# Cloud_Buck_Sch.net
KiCad netlist of a schematic drawn in Altium Designer
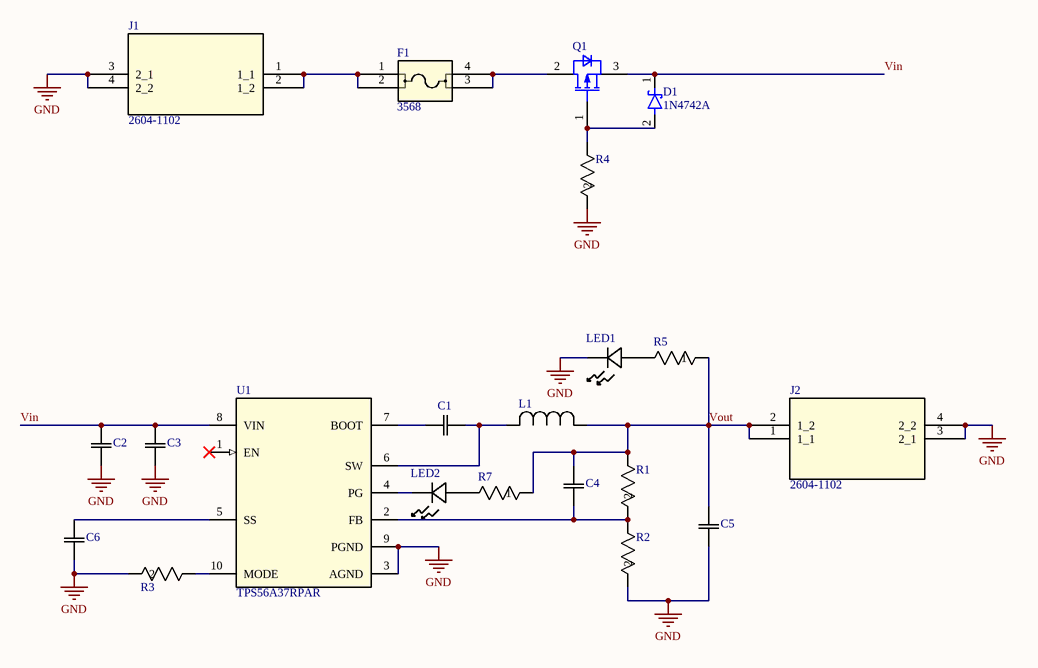
[diagram p0: Cloud_Buck_Sch.SchDoc]

(export (version "E")
  (design (tool "Eeschema 10.0.6"))
  (components
    (comp (ref "C1")
      (value "EMK107B7104KA-T")
      (footprint "cap_UMK107ABJ474KA-T_TAY")
      (description "Description")
      (fields (field (name "COPYRIGHT") "Copyright (C) 2025 Ultra Librarian. All rights reserved."))
      (libsource (lib "Cloud_ Buck_Sym") (part "EMK107B7104KA-T"))
    )
    (comp (ref "C2")
      (value "MSASU32MSB5106KPNA01")
      (footprint "CAP_MSAS32-M_TAY")
      (description "Description")
      (fields (field (name "COPYRIGHT") "Copyright (C) 2026 Ultra Librarian. All rights reserved."))
      (libsource (lib "Cloud_ Buck_Sym") (part "MSASU32MSB5106KPNA01"))
    )
    (comp (ref "C3")
      (value "CC0805KRX7R9BB104")
      (footprint "CC0805N_YAG")
      (description "Description")
      (fields (field (name "COPYRIGHT") "Copyright (C) 2025 Ultra Librarian. All rights reserved."))
      (libsource (lib "Cloud_ Buck_Sym") (part "CC0805KRX7R9BB104"))
    )
    (comp (ref "C4")
      (value "GRM1885C1H101JA01D")
      (footprint "CAP_188_MUR")
      (description "CAP CER 100PF 50V C0G/NP0 0603")
      (fields (field (name "COPYRIGHT") "Copyright (C) 2026 Ultra Librarian. All rights reserved."))
      (libsource (lib "Cloud_ Buck_Sym") (part "GRM1885C1H101JA01D"))
    )
    (comp (ref "C5")
      (value "GRM32ER61C476KE15L")
      (footprint "G-32_MUR")
      (description "Description")
      (fields (field (name "COPYRIGHT") "Copyright (C) 2025 Ultra Librarian. All rights reserved."))
      (libsource (lib "Cloud_ Buck_Sym") (part "GRM32ER61C476KE15L"))
    )
    (comp (ref "C6")
      (value "GRM155R71C223KA01D")
      (footprint "G-155_MUR")
      (description "Description")
      (fields (field (name "COPYRIGHT") "Copyright (C) 2026 Ultra Librarian. All rights reserved."))
      (libsource (lib "Cloud_ Buck_Sym") (part "GRM155R71C223KA01D"))
    )
    (comp (ref "D1")
      (value "1N4742A")
      (footprint "DIOAD1036W78L463D237")
      (description "Zener Diode, Single, Two Terminal, 12V V(Z), 5%, DO-204AL")
      (fields (field (name "MF") "ON Semiconductor"))
      (libsource (lib "Cloud_ Buck_Sym") (part "1N4742A"))
    )
    (comp (ref "F1")
      (value "3568")
      (footprint "3568_KEY")
      (description "Description")
      (fields (field (name "COPYRIGHT") "Copyright (C) 2026 Ultra Librarian. All rights reserved."))
      (libsource (lib "Cloud_ Buck_Sym") (part "3568"))
    )
    (comp (ref "J1")
      (value "2604-1102")
      (footprint "CONN2_2604-1102_WAG")
      (description "Description")
      (fields (field (name "COPYRIGHT") "Copyright (C) 2025 Ultra Librarian. All rights reserved."))
      (libsource (lib "Cloud_ Buck_Sym") (part "2604-1102"))
    )
    (comp (ref "J2")
      (value "2604-1102")
      (footprint "CONN2_2604-1102_WAG")
      (description "Description")
      (fields (field (name "COPYRIGHT") "Copyright (C) 2025 Ultra Librarian. All rights reserved."))
      (libsource (lib "") (part "2604-1102_1"))
    )
    (comp (ref "L1")
      (value "XAL7070-332MEC")
      (footprint "IND_XAL7070_COC")
      (description "Description")
      (fields (field (name "COPYRIGHT") "Copyright (C) 2026 Ultra Librarian. All rights reserved."))
      (libsource (lib "Cloud_ Buck_Sym") (part "XAL7070-332MEC"))
    )
    (comp (ref "LED1")
      (value "LTST-C170KGKT")
      (footprint "LED_LTST-C170KGKT_LTO")
      (description "Description")
      (fields (field (name "COPYRIGHT") "Copyright (C) 2025 Ultra Librarian. All rights reserved."))
      (libsource (lib "Cloud_ Buck_Sym") (part "LTST-C170KGKT"))
    )
    (comp (ref "LED2")
      (value "LTST-C170KGKT")
      (footprint "LED_LTST-C170KGKT_LTO")
      (description "Description")
      (fields (field (name "COPYRIGHT") "Copyright (C) 2025 Ultra Librarian. All rights reserved."))
      (libsource (lib "Cloud_ Buck_Sym") (part "LTST-C170KGKT"))
    )
    (comp (ref "Q1")
      (value "IRF4905")
      (footprint "IFX-PG-TO220-3-904-1")
      (description "OptiMOS - P2 Power-Transistor, P-channel-Enhancement mode, VDS -30V")
      (fields (field (name "MANUFACTURER") "Infineon Technologies"))
      (libsource (lib "Cloud_ Buck_Sym") (part "IRF4905"))
    )
    (comp (ref "R1")
      (value "ERJ-6ENF7322V")
      (footprint "RC0805N_PAN")
      (description "Description")
      (fields (field (name "COPYRIGHT") "Copyright (C) 2026 Ultra Librarian. All rights reserved."))
      (libsource (lib "Cloud_ Buck_Sym") (part "ERJ-6ENF7322V"))
    )
    (comp (ref "R2")
      (value "CRCW060310K0FKEA")
      (footprint "RES_CRCW_0603")
      (description "D11/CRCW0603 100 10K 1% ET1 e3")
      (fields (field (name "COPYRIGHT") "Copyright (C) 2025 Ultra Librarian. All rights reserved."))
      (libsource (lib "Cloud_ Buck_Sym") (part "CRCW060310K0FKEA"))
    )
    (comp (ref "R3")
      (value "CRCW040252K3FKED")
      (footprint "RES_CRCW_0402")
      (description "D10/CRCW0402 100 52K3 1% ET7 e3")
      (fields (field (name "COPYRIGHT") "Copyright (C) 2026 Ultra Librarian. All rights reserved."))
      (libsource (lib "Cloud_ Buck_Sym") (part "CRCW040252K3FKED"))
    )
    (comp (ref "R4")
      (value "CRCW080510K0FKEA")
      (footprint "RES_CRCW_0805")
      (description "D12/CRCW0805 100 10K 1% ET1 e3")
      (fields (field (name "COPYRIGHT") "Copyright (C) 2025 Ultra Librarian. All rights reserved."))
      (libsource (lib "Cloud_ Buck_Sym") (part "CRCW080510K0FKEA"))
    )
    (comp (ref "R5")
      (value "RC0805FR-071K5L")
      (footprint "RC0805N_YAG")
      (description "Description")
      (fields (field (name "COPYRIGHT") "Copyright (C) 2025 Ultra Librarian. All rights reserved."))
      (libsource (lib "Cloud_ Buck_Sym") (part "RC0805FR-071K5L"))
    )
    (comp (ref "R7")
      (value "RC0805FR-071K5L")
      (footprint "RC0805N_YAG")
      (description "Description")
      (fields (field (name "COPYRIGHT") "Copyright (C) 2025 Ultra Librarian. All rights reserved."))
      (libsource (lib "Cloud_ Buck_Sym") (part "RC0805FR-071K5L"))
    )
    (comp (ref "U1")
      (value "TPS56A37RPAR")
      (footprint "RPA0010A-MFG")
      (description "4.5V to 28V input, 10A synchronous buck converter 10-VQFN-HR -40 to 150")
      (fields (field (name "COPYRIGHT") "Copyright (C) 2026 Ultra Librarian. All rights reserved."))
      (libsource (lib "Cloud_ Buck_Sym") (part "TPS56A37RPAR"))
    )
  )
  (nets
    (net (code "1") (name "/Vin") (class "Default")
      (node (ref "C2") (pin "2") (pinfunction "2_2") (pintype "passive"))
      (node (ref "C3") (pin "2") (pinfunction "2_2") (pintype "passive"))
      (node (ref "D1") (pin "1") (pinfunction "K_1") (pintype "passive"))
      (node (ref "Q1") (pin "3") (pinfunction "SOURCE_3") (pintype "passive"))
      (node (ref "U1") (pin "8") (pinfunction "VIN_8") (pintype "power_in"))
    )
    (net (code "2") (name "/Vout") (class "Default")
      (node (ref "C4") (pin "2") (pinfunction "2_2") (pintype "passive"))
      (node (ref "C5") (pin "2") (pinfunction "2_2") (pintype "passive"))
      (node (ref "J2") (pin "1") (pinfunction "1_1_1") (pintype "passive"))
      (node (ref "J2") (pin "2") (pinfunction "1_2_2") (pintype "passive"))
      (node (ref "L1") (pin "1") (pinfunction "1_1") (pintype "passive"))
      (node (ref "R1") (pin "1") (pinfunction "1_1") (pintype "passive"))
      (node (ref "R5") (pin "1") (pinfunction "1_1") (pintype "passive"))
      (node (ref "R7") (pin "1") (pinfunction "1_1") (pintype "passive"))
    )
    (net (code "3") (name "GND") (class "Default")
      (node (ref "C2") (pin "1") (pinfunction "1_1") (pintype "passive"))
      (node (ref "C3") (pin "1") (pinfunction "1_1") (pintype "passive"))
      (node (ref "C5") (pin "1") (pinfunction "1_1") (pintype "passive"))
      (node (ref "C6") (pin "1") (pinfunction "1_1") (pintype "passive"))
      (node (ref "J1") (pin "3") (pinfunction "2_1_3") (pintype "passive"))
      (node (ref "J1") (pin "4") (pinfunction "2_2_4") (pintype "passive"))
      (node (ref "J2") (pin "3") (pinfunction "2_1_3") (pintype "passive"))
      (node (ref "J2") (pin "4") (pinfunction "2_2_4") (pintype "passive"))
      (node (ref "LED1") (pin "1") (pinfunction "1_1") (pintype "passive"))
      (node (ref "R2") (pin "2") (pinfunction "2_2") (pintype "passive"))
      (node (ref "R3") (pin "2") (pinfunction "2_2") (pintype "passive"))
      (node (ref "R4") (pin "2") (pinfunction "2_2") (pintype "passive"))
      (node (ref "U1") (pin "3") (pinfunction "AGND_3") (pintype "power_in"))
      (node (ref "U1") (pin "9") (pinfunction "PGND_9") (pintype "power_in"))
    )
    (net (code "4") (name "Net-(D1-A)") (class "Default")
      (node (ref "D1") (pin "2") (pinfunction "A_2") (pintype "passive"))
      (node (ref "Q1") (pin "1") (pinfunction "GATE_1") (pintype "passive"))
      (node (ref "R4") (pin "1") (pinfunction "1_1") (pintype "passive"))
    )
    (net (code "5") (name "Net-(J1-1_1)") (class "Default")
      (node (ref "F1") (pin "1") (pinfunction "1_1") (pintype "passive"))
      (node (ref "F1") (pin "2") (pinfunction "2_2") (pintype "passive"))
      (node (ref "J1") (pin "1") (pinfunction "1_1_1") (pintype "passive"))
      (node (ref "J1") (pin "2") (pinfunction "1_2_2") (pintype "passive"))
    )
    (net (code "6") (name "Net-(LED1-Pad2)") (class "Default")
      (node (ref "LED1") (pin "2") (pinfunction "2_2") (pintype "passive"))
      (node (ref "R5") (pin "2") (pinfunction "2_2") (pintype "passive"))
    )
    (net (code "7") (name "Net-(LED2-Pad2)") (class "Default")
      (node (ref "LED2") (pin "2") (pinfunction "2_2") (pintype "passive"))
      (node (ref "R7") (pin "2") (pinfunction "2_2") (pintype "passive"))
    )
    (net (code "8") (name "Net-(Q1-DRAIN)") (class "Default")
      (node (ref "F1") (pin "3") (pinfunction "3_3") (pintype "passive"))
      (node (ref "F1") (pin "4") (pinfunction "4_4") (pintype "passive"))
      (node (ref "Q1") (pin "2") (pinfunction "DRAIN_2") (pintype "passive"))
    )
    (net (code "9") (name "Net-(U1-BOOT)") (class "Default")
      (node (ref "C1") (pin "1") (pinfunction "1_1") (pintype "passive"))
      (node (ref "U1") (pin "7") (pinfunction "BOOT_7") (pintype "passive"))
    )
    (net (code "10") (name "Net-(U1-FB)") (class "Default")
      (node (ref "C4") (pin "1") (pinfunction "1_1") (pintype "passive"))
      (node (ref "R1") (pin "2") (pinfunction "2_2") (pintype "passive"))
      (node (ref "R2") (pin "1") (pinfunction "1_1") (pintype "passive"))
      (node (ref "U1") (pin "2") (pinfunction "FB_2") (pintype "passive"))
    )
    (net (code "11") (name "Net-(U1-MODE)") (class "Default")
      (node (ref "R3") (pin "1") (pinfunction "1_1") (pintype "passive"))
      (node (ref "U1") (pin "10") (pinfunction "MODE_10") (pintype "passive"))
    )
    (net (code "12") (name "Net-(U1-PG)") (class "Default")
      (node (ref "LED2") (pin "1") (pinfunction "1_1") (pintype "passive"))
      (node (ref "U1") (pin "4") (pinfunction "PG_4") (pintype "open_collector"))
    )
    (net (code "13") (name "Net-(U1-SS)") (class "Default")
      (node (ref "C6") (pin "2") (pinfunction "2_2") (pintype "passive"))
      (node (ref "U1") (pin "5") (pinfunction "SS_5") (pintype "passive"))
    )
    (net (code "14") (name "Net-(U1-SW)") (class "Default")
      (node (ref "C1") (pin "2") (pinfunction "2_2") (pintype "passive"))
      (node (ref "L1") (pin "2") (pinfunction "2_2") (pintype "passive"))
      (node (ref "U1") (pin "6") (pinfunction "SW_6") (pintype "passive"))
    )
    (net (code "15") (name "unconnected-(U1-EN-Pad1)") (class "Default")
      (node (ref "U1") (pin "1") (pinfunction "EN_1") (pintype "input+no_connect"))
    )
  )
)
